# STM32F446RE_subcircuit.net
KiCad netlist of a schematic drawn in EAGLE
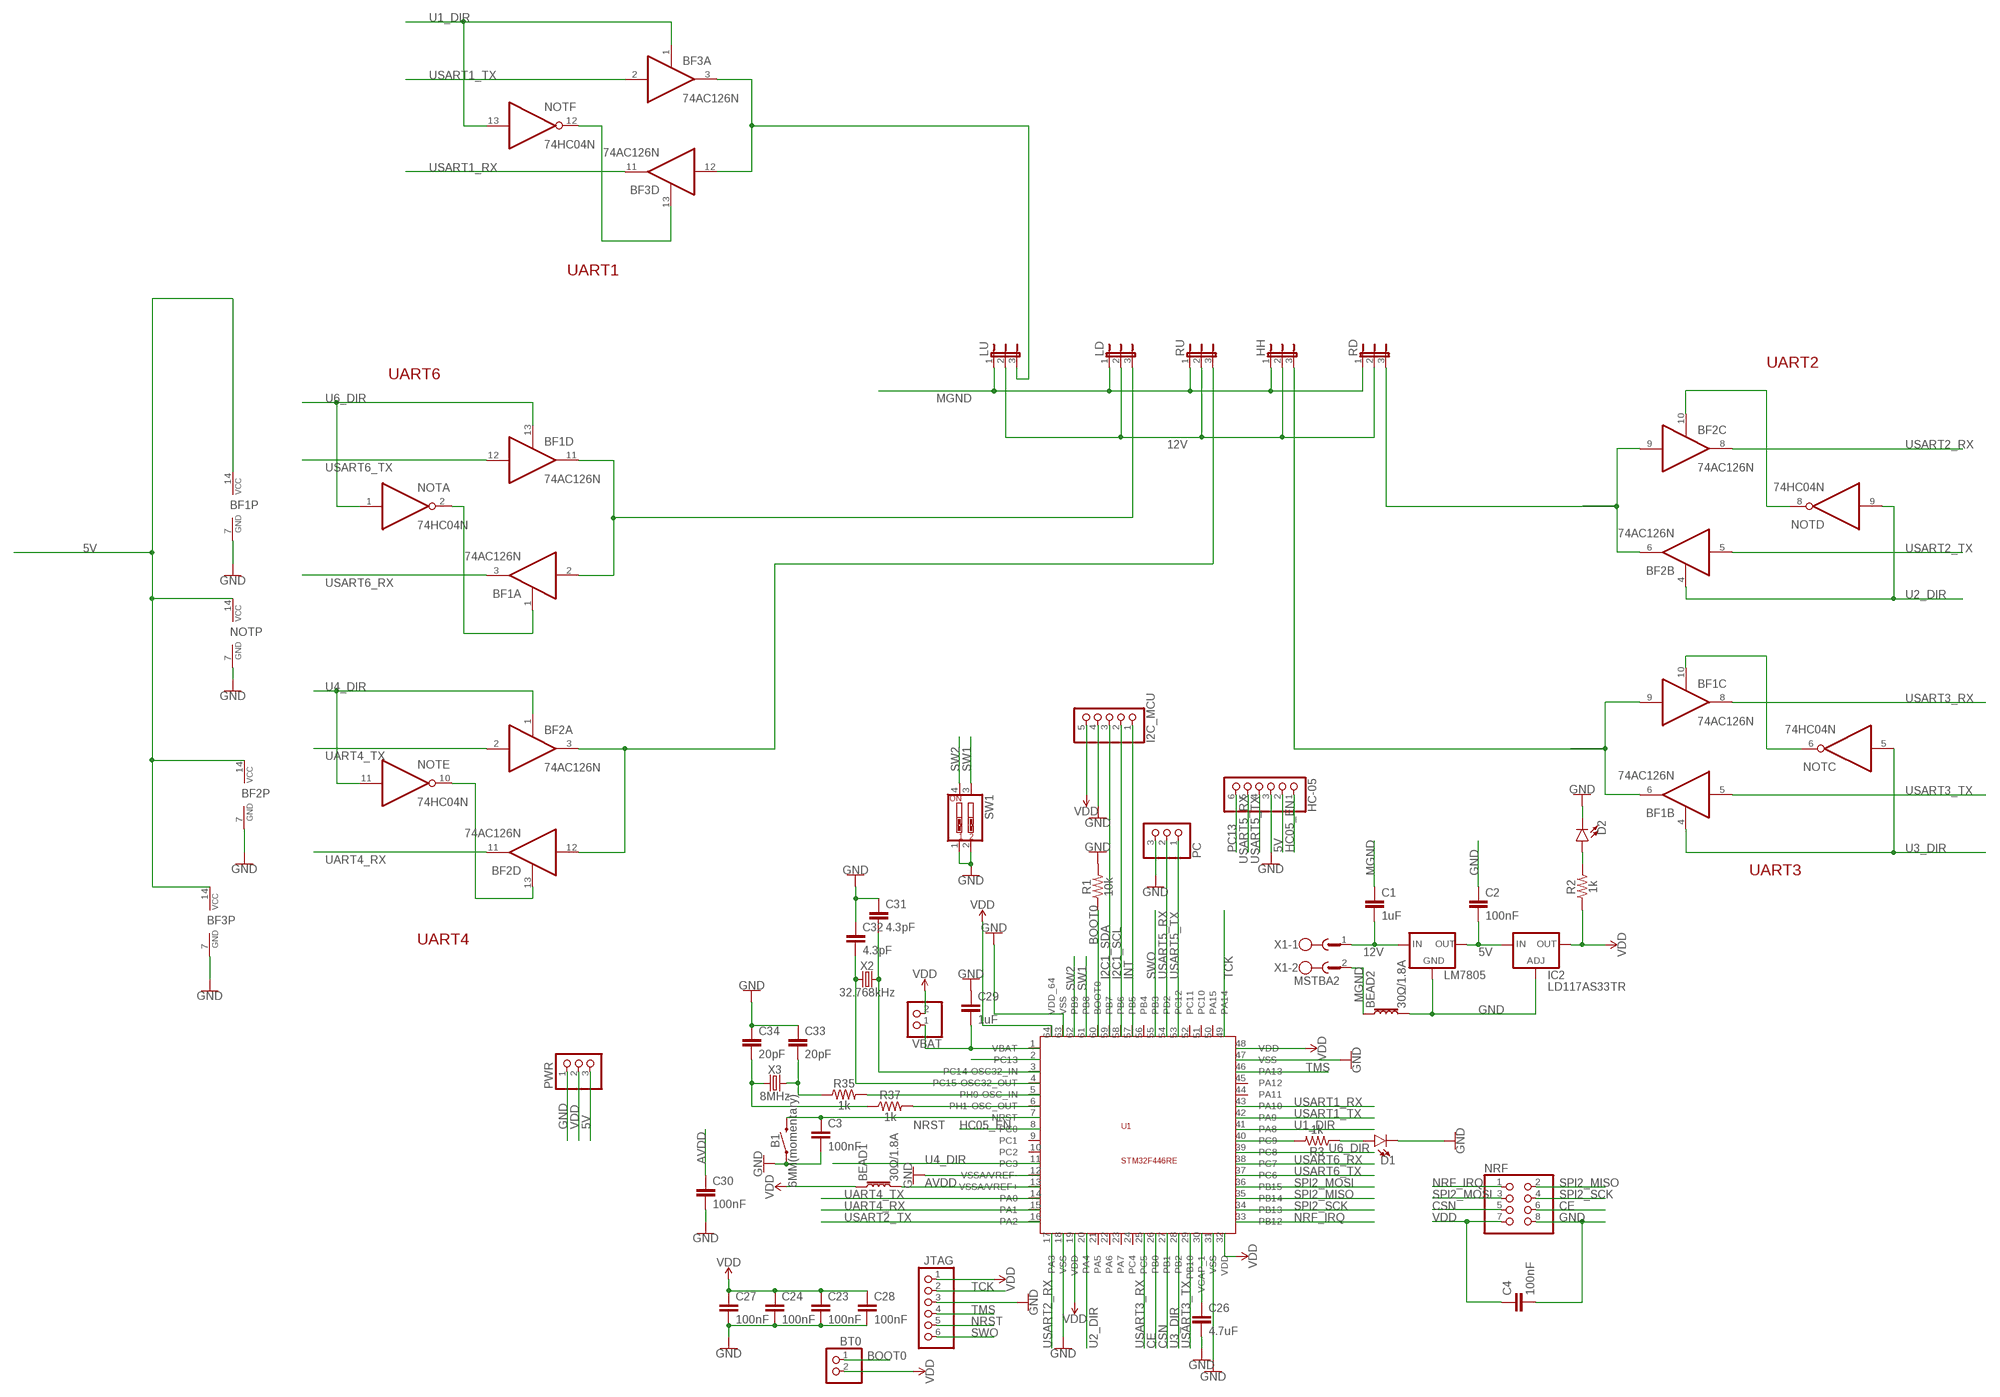
[diagram p0: schematic, sheet 1]

(export (version "E")
  (design (tool "Eeschema 10.0.6"))
  (components
    (comp (ref "B1")
      (value "6MM(momentary)")
      (footprint "eagle-import:TACTILE_SWITCH_PTH_6.0MM")
      (libsource (lib "eagle-import") (part "MOMENTARY-SWITCH-SPST-PTH-6.0MM"))
    )
    (comp (ref "BEAD1")
      (value "30Ω/1.8A")
      (footprint "eagle-import:0603")
      (libsource (lib "eagle-import") (part "FERRITE_BEAD-0603"))
    )
    (comp (ref "BEAD2")
      (value "30Ω/1.8A")
      (footprint "eagle-import:0603")
      (libsource (lib "eagle-import") (part "FERRITE_BEAD-0603"))
    )
    (comp (ref "BF1")
      (value "74AC126N")
      (footprint "eagle-import:DIL14")
      (libsource (lib "eagle-import") (part "74126NAC"))
    )
    (comp (ref "BF2")
      (value "74AC126N")
      (footprint "eagle-import:DIL14")
      (libsource (lib "eagle-import") (part "74126NAC"))
    )
    (comp (ref "BF3")
      (value "74AC126N")
      (footprint "eagle-import:DIL14")
      (libsource (lib "eagle-import") (part "74xx-eu_85_74126NAC"))
    )
    (comp (ref "BT0")
      (value "PINHD-1X2")
      (footprint "eagle-import:1X02")
      (libsource (lib "eagle-import") (part "PINHD-1X2"))
    )
    (comp (ref "C1")
      (value "1uF")
      (footprint "eagle-import:C050-030-075")
      (libsource (lib "eagle-import") (part "C5P"))
    )
    (comp (ref "C2")
      (value "100nF")
      (footprint "eagle-import:C025-030X050")
      (libsource (lib "eagle-import") (part "C2.5P"))
    )
    (comp (ref "C3")
      (value "100nF")
      (footprint "eagle-import:C025-030X050")
      (libsource (lib "eagle-import") (part "C2.5P"))
    )
    (comp (ref "C4")
      (value "100nF")
      (footprint "eagle-import:C025-030X050")
      (libsource (lib "eagle-import") (part "C2.5P"))
    )
    (comp (ref "C23")
      (value "100nF")
      (footprint "eagle-import:C025-030X050")
      (libsource (lib "eagle-import") (part "C2.5P"))
    )
    (comp (ref "C24")
      (value "100nF")
      (footprint "eagle-import:C025-030X050")
      (libsource (lib "eagle-import") (part "C2.5P"))
    )
    (comp (ref "C26")
      (value "4.7uF")
      (footprint "eagle-import:C050-030-075")
      (libsource (lib "eagle-import") (part "C5P"))
    )
    (comp (ref "C27")
      (value "100nF")
      (footprint "eagle-import:C025-030X050")
      (libsource (lib "eagle-import") (part "C2.5P"))
    )
    (comp (ref "C28")
      (value "100nF")
      (footprint "eagle-import:C025-030X050")
      (libsource (lib "eagle-import") (part "C2.5P"))
    )
    (comp (ref "C29")
      (value "1uF")
      (footprint "eagle-import:C050-030-075")
      (libsource (lib "eagle-import") (part "C5P"))
    )
    (comp (ref "C30")
      (value "100nF")
      (footprint "eagle-import:C025-030X050")
      (libsource (lib "eagle-import") (part "C2.5P"))
    )
    (comp (ref "C31")
      (value "4.3pF")
      (footprint "eagle-import:C025-030X050")
      (libsource (lib "eagle-import") (part "C2.5P"))
    )
    (comp (ref "C32")
      (value "4.3pF")
      (footprint "eagle-import:C025-030X050")
      (libsource (lib "eagle-import") (part "C2.5P"))
    )
    (comp (ref "C33")
      (value "20pF")
      (footprint "eagle-import:C025-030X050")
      (libsource (lib "eagle-import") (part "C2.5P"))
    )
    (comp (ref "C34")
      (value "20pF")
      (footprint "eagle-import:C025-030X050")
      (libsource (lib "eagle-import") (part "C2.5P"))
    )
    (comp (ref "D1")
      (value "LED5MM")
      (footprint "eagle-import:LED_5MM")
      (libsource (lib "eagle-import") (part "LED5MM"))
    )
    (comp (ref "D2")
      (value "LED5MM")
      (footprint "eagle-import:LED_5MM")
      (libsource (lib "eagle-import") (part "LED5MM"))
    )
    (comp (ref "HC-05")
      (value "PINHD-1X6")
      (footprint "eagle-import:1X06")
      (libsource (lib "eagle-import") (part "PINHD-1X6"))
    )
    (comp (ref "HH")
      (value "JP2E")
      (footprint "eagle-import:JP2")
      (libsource (lib "eagle-import") (part "JP2E"))
    )
    (comp (ref "I2C_MCU")
      (value "PINHD-1X5")
      (footprint "eagle-import:1X05")
      (libsource (lib "eagle-import") (part "PINHD-1X5"))
    )
    (comp (ref "IC2")
      (value "LD117AS33TR")
      (footprint "eagle-import:SOT223")
      (libsource (lib "eagle-import") (part "LD117A?S33TR"))
    )
    (comp (ref "JTAG")
      (value "PINHD-1X6")
      (footprint "eagle-import:1X06")
      (libsource (lib "eagle-import") (part "PINHD-1X6"))
    )
    (comp (ref "LD")
      (value "JP2E")
      (footprint "eagle-import:JP2")
      (libsource (lib "eagle-import") (part "JP2E"))
    )
    (comp (ref "LM7805")
      (value "V_REG_78XX-TO-220")
      (footprint "eagle-import:TO-220-ALT")
      (libsource (lib "eagle-import") (part "V_REG_78XX-TO-220"))
    )
    (comp (ref "LU")
      (value "JP2E")
      (footprint "eagle-import:JP2")
      (libsource (lib "eagle-import") (part "JP2E"))
    )
    (comp (ref "NOT")
      (value "74HC04N")
      (footprint "eagle-import:DIL14")
      (libsource (lib "eagle-import") (part "7404NHC"))
    )
    (comp (ref "NRF")
      (value "PINHD-2X4")
      (footprint "eagle-import:2X04")
      (libsource (lib "eagle-import") (part "PINHD-2X4"))
    )
    (comp (ref "PC")
      (value "PINHD-1X3")
      (footprint "eagle-import:1X03")
      (libsource (lib "eagle-import") (part "PINHD-1X3"))
    )
    (comp (ref "PWR")
      (value "PINHD-1X3")
      (footprint "eagle-import:1X03")
      (libsource (lib "eagle-import") (part "PINHD-1X3"))
    )
    (comp (ref "R1")
      (value "10k")
      (footprint "eagle-import:AXIAL-0.3")
      (libsource (lib "eagle-import") (part "10KOHM-HORIZ-1/4W-1%"))
    )
    (comp (ref "R2")
      (value "1k")
      (footprint "eagle-import:AXIAL-0.3")
      (libsource (lib "eagle-import") (part "1KOHM-HORIZ-1/4W-1%"))
    )
    (comp (ref "R3")
      (value "1k")
      (footprint "eagle-import:AXIAL-0.3")
      (libsource (lib "eagle-import") (part "1KOHM-HORIZ-1/4W-5%"))
    )
    (comp (ref "R35")
      (value "1k")
      (footprint "eagle-import:AXIAL-0.3")
      (libsource (lib "eagle-import") (part "10KOHM-HORIZ-1/4W-1%"))
    )
    (comp (ref "R37")
      (value "1k")
      (footprint "eagle-import:AXIAL-0.3")
      (libsource (lib "eagle-import") (part "10KOHM-HORIZ-1/4W-1%"))
    )
    (comp (ref "RD")
      (value "JP2E")
      (footprint "eagle-import:JP2")
      (libsource (lib "eagle-import") (part "JP2E"))
    )
    (comp (ref "RU")
      (value "JP2E")
      (footprint "eagle-import:JP2")
      (libsource (lib "eagle-import") (part "JP2E"))
    )
    (comp (ref "SW1")
      (value "SW_DIP-2")
      (footprint "eagle-import:EDG-02")
      (libsource (lib "eagle-import") (part "SW_DIP-2"))
    )
    (comp (ref "U1")
      (value "STM32F446RE")
      (footprint "eagle-import:QFP50P1200X1200X160-64N")
      (libsource (lib "eagle-import") (part "STM32F446RE"))
    )
    (comp (ref "VBAT")
      (value "PINHD-1X2")
      (footprint "eagle-import:1X02")
      (libsource (lib "eagle-import") (part "PINHD-1X2"))
    )
    (comp (ref "X1")
      (value "MSTBA2")
      (footprint "eagle-import:MSTBA2")
      (fields (field (name "MF") "FARNELL") (field (name "MPN") "1757242"))
      (libsource (lib "eagle-import") (part "MSTBA2"))
    )
    (comp (ref "X2")
      (value "32.768kHz")
      (footprint "eagle-import:CRYSTAL-PTH-2X6-CYL")
      (libsource (lib "eagle-import") (part "CRYSTAL-32.768KHZPTH-2X6"))
    )
    (comp (ref "X3")
      (value "8MHz")
      (footprint "eagle-import:HC49UP")
      (libsource (lib "eagle-import") (part "CRYSTAL-8MHZSMD-HC49UP"))
    )
  )
  (nets
    (net (code "1") (name "/5V") (class "Default")
      (node (ref "BF1") (pin "14") (pinfunction "VCC_14") (pintype "power_in"))
      (node (ref "BF2") (pin "14") (pinfunction "VCC_14") (pintype "power_in"))
      (node (ref "BF3") (pin "14") (pinfunction "VCC_14") (pintype "power_in"))
      (node (ref "C2") (pin "2") (pinfunction "2_2") (pintype "passive"))
      (node (ref "HC-05") (pin "2") (pinfunction "2_2") (pintype "passive"))
      (node (ref "IC2") (pin "3") (pinfunction "IN_3") (pintype "input"))
      (node (ref "LM7805") (pin "OUT") (pinfunction "OUT_OUT") (pintype "passive"))
      (node (ref "NOT") (pin "14") (pinfunction "VCC_14") (pintype "power_in"))
      (node (ref "PWR") (pin "3") (pinfunction "3_3") (pintype "passive"))
    )
    (net (code "2") (name "/12V") (class "Default")
      (node (ref "C1") (pin "2") (pinfunction "2_2") (pintype "passive"))
      (node (ref "HH") (pin "2") (pinfunction "2_2") (pintype "passive"))
      (node (ref "LD") (pin "2") (pinfunction "2_2") (pintype "passive"))
      (node (ref "LM7805") (pin "IN") (pinfunction "IN_IN") (pintype "input"))
      (node (ref "LU") (pin "2") (pinfunction "2_2") (pintype "passive"))
      (node (ref "RD") (pin "2") (pinfunction "2_2") (pintype "passive"))
      (node (ref "RU") (pin "2") (pinfunction "2_2") (pintype "passive"))
      (node (ref "X1") (pin "1") (pinfunction "1_1") (pintype "passive"))
    )
    (net (code "3") (name "/AVDD") (class "Default")
      (node (ref "BEAD1") (pin "2") (pinfunction "2_2") (pintype "passive"))
      (node (ref "C30") (pin "1") (pinfunction "1_1") (pintype "passive"))
      (node (ref "U1") (pin "13") (pinfunction "VSSA/VREF+_13") (pintype "power_in"))
    )
    (net (code "4") (name "/BOOT0") (class "Default")
      (node (ref "BT0") (pin "1") (pinfunction "1_1") (pintype "passive"))
      (node (ref "R1") (pin "P$1") (pinfunction "1_P$1") (pintype "passive"))
      (node (ref "U1") (pin "60") (pinfunction "BOOT0_60") (pintype "input"))
    )
    (net (code "5") (name "/CE") (class "Default")
      (node (ref "NRF") (pin "6") (pinfunction "6_6") (pintype "passive"))
      (node (ref "U1") (pin "26") (pinfunction "PB0_26") (pintype "bidirectional"))
    )
    (net (code "6") (name "/CSN") (class "Default")
      (node (ref "NRF") (pin "5") (pinfunction "5_5") (pintype "passive"))
      (node (ref "U1") (pin "27") (pinfunction "PB1_27") (pintype "bidirectional"))
    )
    (net (code "7") (name "/HC05_EN") (class "Default")
      (node (ref "HC-05") (pin "1") (pinfunction "1_1") (pintype "passive"))
      (node (ref "U1") (pin "8") (pinfunction "PC0_8") (pintype "bidirectional"))
    )
    (net (code "8") (name "/I2C1_SCL") (class "Default")
      (node (ref "I2C_MCU") (pin "2") (pinfunction "2_2") (pintype "passive"))
      (node (ref "U1") (pin "58") (pinfunction "PB6_58") (pintype "bidirectional"))
    )
    (net (code "9") (name "/I2C1_SDA") (class "Default")
      (node (ref "I2C_MCU") (pin "3") (pinfunction "3_3") (pintype "passive"))
      (node (ref "U1") (pin "59") (pinfunction "PB7_59") (pintype "bidirectional"))
    )
    (net (code "10") (name "/INT") (class "Default")
      (node (ref "I2C_MCU") (pin "1") (pinfunction "1_1") (pintype "passive"))
      (node (ref "U1") (pin "57") (pinfunction "PB5_57") (pintype "bidirectional"))
    )
    (net (code "11") (name "/MGND") (class "Default")
      (node (ref "BEAD2") (pin "1") (pinfunction "1_1") (pintype "passive"))
      (node (ref "C1") (pin "1") (pinfunction "1_1") (pintype "passive"))
      (node (ref "HH") (pin "1") (pinfunction "1_1") (pintype "passive"))
      (node (ref "LD") (pin "1") (pinfunction "1_1") (pintype "passive"))
      (node (ref "LU") (pin "1") (pinfunction "1_1") (pintype "passive"))
      (node (ref "RD") (pin "1") (pinfunction "1_1") (pintype "passive"))
      (node (ref "RU") (pin "1") (pinfunction "1_1") (pintype "passive"))
      (node (ref "X1") (pin "2") (pinfunction "1_2") (pintype "passive"))
    )
    (net (code "12") (name "/NRF_IRQ") (class "Default")
      (node (ref "NRF") (pin "1") (pinfunction "1_1") (pintype "passive"))
      (node (ref "U1") (pin "33") (pinfunction "PB12_33") (pintype "bidirectional"))
    )
    (net (code "13") (name "/NRST") (class "Default")
      (node (ref "B1") (pin "3") (pinfunction "2_3") (pintype "passive"))
      (node (ref "C3") (pin "1") (pinfunction "1_1") (pintype "passive"))
      (node (ref "JTAG") (pin "5") (pinfunction "5_5") (pintype "passive"))
      (node (ref "U1") (pin "7") (pinfunction "NRST_7") (pintype "bidirectional"))
    )
    (net (code "14") (name "/PC13") (class "Default")
      (node (ref "HC-05") (pin "6") (pinfunction "6_6") (pintype "passive"))
      (node (ref "U1") (pin "2") (pinfunction "PC13_2") (pintype "bidirectional"))
    )
    (net (code "15") (name "/SPI2_MISO") (class "Default")
      (node (ref "NRF") (pin "2") (pinfunction "2_2") (pintype "passive"))
      (node (ref "U1") (pin "35") (pinfunction "PB14_35") (pintype "bidirectional"))
    )
    (net (code "16") (name "/SPI2_MOSI") (class "Default")
      (node (ref "NRF") (pin "3") (pinfunction "3_3") (pintype "passive"))
      (node (ref "U1") (pin "36") (pinfunction "PB15_36") (pintype "bidirectional"))
    )
    (net (code "17") (name "/SPI2_SCK") (class "Default")
      (node (ref "NRF") (pin "4") (pinfunction "4_4") (pintype "passive"))
      (node (ref "U1") (pin "34") (pinfunction "PB13_34") (pintype "bidirectional"))
    )
    (net (code "18") (name "/SW1") (class "Default")
      (node (ref "SW1") (pin "3") (pinfunction "3_3") (pintype "passive"))
      (node (ref "U1") (pin "61") (pinfunction "PB8_61") (pintype "bidirectional"))
    )
    (net (code "19") (name "/SW2") (class "Default")
      (node (ref "SW1") (pin "4") (pinfunction "4_4") (pintype "passive"))
      (node (ref "U1") (pin "62") (pinfunction "PB9_62") (pintype "bidirectional"))
    )
    (net (code "20") (name "/SWO") (class "Default")
      (node (ref "JTAG") (pin "6") (pinfunction "6_6") (pintype "passive"))
      (node (ref "U1") (pin "55") (pinfunction "PB3_55") (pintype "bidirectional"))
    )
    (net (code "21") (name "/TCK") (class "Default")
      (node (ref "JTAG") (pin "2") (pinfunction "2_2") (pintype "passive"))
      (node (ref "U1") (pin "49") (pinfunction "PA14_49") (pintype "bidirectional"))
    )
    (net (code "22") (name "/TMS") (class "Default")
      (node (ref "JTAG") (pin "4") (pinfunction "4_4") (pintype "passive"))
      (node (ref "U1") (pin "46") (pinfunction "PA13_46") (pintype "bidirectional"))
    )
    (net (code "23") (name "/U1_DIR") (class "Default")
      (node (ref "BF3") (pin "1") (pinfunction "OE_1") (pintype "input"))
      (node (ref "NOT") (pin "13") (pinfunction "I_13") (pintype "input"))
      (node (ref "U1") (pin "41") (pinfunction "PA8_41") (pintype "bidirectional"))
    )
    (net (code "24") (name "/U2_DIR") (class "Default")
      (node (ref "BF2") (pin "4") (pinfunction "OE_4") (pintype "input"))
      (node (ref "NOT") (pin "9") (pinfunction "I_9") (pintype "input"))
      (node (ref "U1") (pin "20") (pinfunction "PA4_20") (pintype "bidirectional"))
    )
    (net (code "25") (name "/U3_DIR") (class "Default")
      (node (ref "BF1") (pin "4") (pinfunction "OE_4") (pintype "input"))
      (node (ref "NOT") (pin "5") (pinfunction "I_5") (pintype "input"))
      (node (ref "U1") (pin "28") (pinfunction "PB2_28") (pintype "bidirectional"))
    )
    (net (code "26") (name "/U4_DIR") (class "Default")
      (node (ref "BF2") (pin "1") (pinfunction "OE_1") (pintype "input"))
      (node (ref "NOT") (pin "11") (pinfunction "I_11") (pintype "input"))
      (node (ref "U1") (pin "11") (pinfunction "PC3_11") (pintype "bidirectional"))
    )
    (net (code "27") (name "/U6_DIR") (class "Default")
      (node (ref "BF1") (pin "13") (pinfunction "OE_13") (pintype "input"))
      (node (ref "NOT") (pin "1") (pinfunction "I_1") (pintype "input"))
      (node (ref "U1") (pin "39") (pinfunction "PC8_39") (pintype "bidirectional"))
    )
    (net (code "28") (name "/UART4_RX") (class "Default")
      (node (ref "BF2") (pin "11") (pinfunction "O_11") (pintype "output"))
      (node (ref "U1") (pin "15") (pinfunction "PA1_15") (pintype "bidirectional"))
    )
    (net (code "29") (name "/UART4_TX") (class "Default")
      (node (ref "BF2") (pin "2") (pinfunction "I_2") (pintype "input"))
      (node (ref "U1") (pin "14") (pinfunction "PA0_14") (pintype "bidirectional"))
    )
    (net (code "30") (name "/USART1_RX") (class "Default")
      (node (ref "BF3") (pin "11") (pinfunction "O_11") (pintype "output"))
      (node (ref "U1") (pin "43") (pinfunction "PA10_43") (pintype "bidirectional"))
    )
    (net (code "31") (name "/USART1_TX") (class "Default")
      (node (ref "BF3") (pin "2") (pinfunction "I_2") (pintype "input"))
      (node (ref "U1") (pin "42") (pinfunction "PA9_42") (pintype "bidirectional"))
    )
    (net (code "32") (name "/USART2_RX") (class "Default")
      (node (ref "BF2") (pin "8") (pinfunction "O_8") (pintype "output"))
      (node (ref "U1") (pin "17") (pinfunction "PA3_17") (pintype "bidirectional"))
    )
    (net (code "33") (name "/USART2_TX") (class "Default")
      (node (ref "BF2") (pin "5") (pinfunction "I_5") (pintype "input"))
      (node (ref "U1") (pin "16") (pinfunction "PA2_16") (pintype "bidirectional"))
    )
    (net (code "34") (name "/USART3_RX") (class "Default")
      (node (ref "BF1") (pin "8") (pinfunction "O_8") (pintype "output"))
      (node (ref "U1") (pin "25") (pinfunction "PC5_25") (pintype "bidirectional"))
    )
    (net (code "35") (name "/USART3_TX") (class "Default")
      (node (ref "BF1") (pin "5") (pinfunction "I_5") (pintype "input"))
      (node (ref "U1") (pin "29") (pinfunction "PB10_29") (pintype "bidirectional"))
    )
    (net (code "36") (name "/USART5_RX") (class "Default")
      (node (ref "HC-05") (pin "5") (pinfunction "5_5") (pintype "passive"))
      (node (ref "PC") (pin "2") (pinfunction "2_2") (pintype "passive"))
      (node (ref "U1") (pin "54") (pinfunction "PD2_54") (pintype "bidirectional"))
    )
    (net (code "37") (name "/USART5_TX") (class "Default")
      (node (ref "HC-05") (pin "4") (pinfunction "4_4") (pintype "passive"))
      (node (ref "PC") (pin "1") (pinfunction "1_1") (pintype "passive"))
      (node (ref "U1") (pin "53") (pinfunction "PC12_53") (pintype "bidirectional"))
    )
    (net (code "38") (name "/USART6_RX") (class "Default")
      (node (ref "BF1") (pin "3") (pinfunction "O_3") (pintype "output"))
      (node (ref "U1") (pin "38") (pinfunction "PC7_38") (pintype "bidirectional"))
    )
    (net (code "39") (name "/USART6_TX") (class "Default")
      (node (ref "BF1") (pin "12") (pinfunction "I_12") (pintype "input"))
      (node (ref "U1") (pin "37") (pinfunction "PC6_37") (pintype "bidirectional"))
    )
    (net (code "40") (name "GND") (class "Default")
      (node (ref "B1") (pin "1") (pinfunction "1_1") (pintype "passive"))
      (node (ref "BEAD2") (pin "2") (pinfunction "2_2") (pintype "passive"))
      (node (ref "BF1") (pin "7") (pinfunction "GND_7") (pintype "power_in"))
      (node (ref "BF2") (pin "7") (pinfunction "GND_7") (pintype "power_in"))
      (node (ref "BF3") (pin "7") (pinfunction "GND_7") (pintype "power_in"))
      (node (ref "C2") (pin "1") (pinfunction "1_1") (pintype "passive"))
      (node (ref "C23") (pin "2") (pinfunction "2_2") (pintype "passive"))
      (node (ref "C24") (pin "2") (pinfunction "2_2") (pintype "passive"))
      (node (ref "C26") (pin "2") (pinfunction "2_2") (pintype "passive"))
      (node (ref "C27") (pin "2") (pinfunction "2_2") (pintype "passive"))
      (node (ref "C28") (pin "2") (pinfunction "2_2") (pintype "passive"))
      (node (ref "C29") (pin "1") (pinfunction "1_1") (pintype "passive"))
      (node (ref "C3") (pin "2") (pinfunction "2_2") (pintype "passive"))
      (node (ref "C30") (pin "2") (pinfunction "2_2") (pintype "passive"))
      (node (ref "C31") (pin "1") (pinfunction "1_1") (pintype "passive"))
      (node (ref "C32") (pin "1") (pinfunction "1_1") (pintype "passive"))
      (node (ref "C33") (pin "1") (pinfunction "1_1") (pintype "passive"))
      (node (ref "C34") (pin "1") (pinfunction "1_1") (pintype "passive"))
      (node (ref "C4") (pin "2") (pinfunction "2_2") (pintype "passive"))
      (node (ref "D1") (pin "K") (pinfunction "C_K") (pintype "passive"))
      (node (ref "D2") (pin "K") (pinfunction "C_K") (pintype "passive"))
      (node (ref "HC-05") (pin "3") (pinfunction "3_3") (pintype "passive"))
      (node (ref "I2C_MCU") (pin "4") (pinfunction "4_4") (pintype "passive"))
      (node (ref "IC2") (pin "1") (pinfunction "ADJ_1") (pintype "input"))
      (node (ref "JTAG") (pin "3") (pinfunction "3_3") (pintype "passive"))
      (node (ref "LM7805") (pin "GND") (pinfunction "GND_GND") (pintype "input"))
      (node (ref "NOT") (pin "7") (pinfunction "GND_7") (pintype "power_in"))
      (node (ref "NRF") (pin "8") (pinfunction "8_8") (pintype "passive"))
      (node (ref "PC") (pin "3") (pinfunction "3_3") (pintype "passive"))
      (node (ref "PWR") (pin "1") (pinfunction "1_1") (pintype "passive"))
      (node (ref "R1") (pin "P$2") (pinfunction "2_P$2") (pintype "passive"))
      (node (ref "SW1") (pin "1") (pinfunction "1_1") (pintype "passive"))
      (node (ref "SW1") (pin "2") (pinfunction "2_2") (pintype "passive"))
      (node (ref "U1") (pin "12") (pinfunction "VSSA/VREF-_12") (pintype "power_in"))
      (node (ref "U1") (pin "18") (pinfunction "VSS_18") (pintype "power_in"))
      (node (ref "U1") (pin "31") (pinfunction "VSS_31") (pintype "power_in"))
      (node (ref "U1") (pin "47") (pinfunction "VSS_47") (pintype "power_in"))
      (node (ref "U1") (pin "63") (pinfunction "VSS_63") (pintype "power_in"))
    )
    (net (code "41") (name "Net-(BF1A-I)") (class "Default")
      (node (ref "BF1") (pin "11") (pinfunction "O_11") (pintype "output"))
      (node (ref "BF1") (pin "2") (pinfunction "I_2") (pintype "input"))
      (node (ref "LD") (pin "3") (pinfunction "3_3") (pintype "passive"))
    )
    (net (code "42") (name "Net-(BF1A-OE)") (class "Default")
      (node (ref "BF1") (pin "1") (pinfunction "OE_1") (pintype "input"))
      (node (ref "NOT") (pin "2") (pinfunction "O_2") (pintype "output"))
    )
    (net (code "43") (name "Net-(BF1B-O)") (class "Default")
      (node (ref "BF1") (pin "6") (pinfunction "O_6") (pintype "output"))
      (node (ref "BF1") (pin "9") (pinfunction "I_9") (pintype "input"))
      (node (ref "HH") (pin "3") (pinfunction "3_3") (pintype "passive"))
    )
    (net (code "44") (name "Net-(BF1C-OE)") (class "Default")
      (node (ref "BF1") (pin "10") (pinfunction "OE_10") (pintype "input"))
      (node (ref "NOT") (pin "6") (pinfunction "O_6") (pintype "output"))
    )
    (net (code "45") (name "Net-(BF2A-O)") (class "Default")
      (node (ref "BF2") (pin "12") (pinfunction "I_12") (pintype "input"))
      (node (ref "BF2") (pin "3") (pinfunction "O_3") (pintype "output"))
      (node (ref "RU") (pin "3") (pinfunction "3_3") (pintype "passive"))
    )
    (net (code "46") (name "Net-(BF2B-O)") (class "Default")
      (node (ref "BF2") (pin "6") (pinfunction "O_6") (pintype "output"))
      (node (ref "BF2") (pin "9") (pinfunction "I_9") (pintype "input"))
      (node (ref "RD") (pin "3") (pinfunction "3_3") (pintype "passive"))
    )
    (net (code "47") (name "Net-(BF2C-OE)") (class "Default")
      (node (ref "BF2") (pin "10") (pinfunction "OE_10") (pintype "input"))
      (node (ref "NOT") (pin "8") (pinfunction "O_8") (pintype "output"))
    )
    (net (code "48") (name "Net-(BF2D-OE)") (class "Default")
      (node (ref "BF2") (pin "13") (pinfunction "OE_13") (pintype "input"))
      (node (ref "NOT") (pin "10") (pinfunction "O_10") (pintype "output"))
    )
    (net (code "49") (name "Net-(BF3A-O)") (class "Default")
      (node (ref "BF3") (pin "12") (pinfunction "I_12") (pintype "input"))
      (node (ref "BF3") (pin "3") (pinfunction "O_3") (pintype "output"))
      (node (ref "LU") (pin "3") (pinfunction "3_3") (pintype "passive"))
    )
    (net (code "50") (name "Net-(BF3D-OE)") (class "Default")
      (node (ref "BF3") (pin "13") (pinfunction "OE_13") (pintype "input"))
      (node (ref "NOT") (pin "12") (pinfunction "O_12") (pintype "output"))
    )
    (net (code "51") (name "Net-(R2-2)") (class "Default")
      (node (ref "D2") (pin "A") (pinfunction "A_A") (pintype "passive"))
      (node (ref "R2") (pin "P$2") (pinfunction "2_P$2") (pintype "passive"))
    )
    (net (code "52") (name "Net-(R3-1)") (class "Default")
      (node (ref "D1") (pin "A") (pinfunction "A_A") (pintype "passive"))
      (node (ref "R3") (pin "P$1") (pinfunction "1_P$1") (pintype "passive"))
    )
    (net (code "53") (name "Net-(R3-2)") (class "Default")
      (node (ref "R3") (pin "P$2") (pinfunction "2_P$2") (pintype "passive"))
      (node (ref "U1") (pin "40") (pinfunction "PC9_40") (pintype "bidirectional"))
    )
    (net (code "54") (name "Net-(R35-1)") (class "Default")
      (node (ref "C33") (pin "2") (pinfunction "2_2") (pintype "passive"))
      (node (ref "R35") (pin "P$1") (pinfunction "1_P$1") (pintype "passive"))
      (node (ref "X3") (pin "2") (pinfunction "2_2") (pintype "passive"))
    )
    (net (code "55") (name "Net-(R35-2)") (class "Default")
      (node (ref "R35") (pin "P$2") (pinfunction "2_P$2") (pintype "passive"))
      (node (ref "U1") (pin "5") (pinfunction "PH0-OSC_IN_5") (pintype "input"))
    )
    (net (code "56") (name "Net-(R37-1)") (class "Default")
      (node (ref "C34") (pin "2") (pinfunction "2_2") (pintype "passive"))
      (node (ref "R37") (pin "P$1") (pinfunction "1_P$1") (pintype "passive"))
      (node (ref "X3") (pin "1") (pinfunction "1_1") (pintype "passive"))
    )
    (net (code "57") (name "Net-(R37-2)") (class "Default")
      (node (ref "R37") (pin "P$2") (pinfunction "2_P$2") (pintype "passive"))
      (node (ref "U1") (pin "6") (pinfunction "PH1-OSC_OUT_6") (pintype "output"))
    )
    (net (code "58") (name "Net-(U1-PC14-OSC32_IN)") (class "Default")
      (node (ref "C31") (pin "2") (pinfunction "2_2") (pintype "passive"))
      (node (ref "U1") (pin "3") (pinfunction "PC14-OSC32_IN_3") (pintype "input"))
      (node (ref "X2") (pin "2") (pinfunction "2_2") (pintype "passive"))
    )
    (net (code "59") (name "Net-(U1-PC15-OSC32_OUT)") (class "Default")
      (node (ref "C32") (pin "2") (pinfunction "2_2") (pintype "passive"))
      (node (ref "U1") (pin "4") (pinfunction "PC15-OSC32_OUT_4") (pintype "output"))
      (node (ref "X2") (pin "1") (pinfunction "1_1") (pintype "passive"))
    )
    (net (code "60") (name "Net-(U1-VBAT)") (class "Default")
      (node (ref "C29") (pin "2") (pinfunction "2_2") (pintype "passive"))
      (node (ref "U1") (pin "1") (pinfunction "VBAT_1") (pintype "power_in"))
      (node (ref "VBAT") (pin "1") (pinfunction "1_1") (pintype "passive"))
    )
    (net (code "61") (name "Net-(U1-VCAP_1)") (class "Default")
      (node (ref "C26") (pin "1") (pinfunction "1_1") (pintype "passive"))
      (node (ref "U1") (pin "30") (pinfunction "VCAP_1_30") (pintype "power_in"))
    )
    (net (code "62") (name "VDD") (class "Default")
      (node (ref "BEAD1") (pin "1") (pinfunction "1_1") (pintype "passive"))
      (node (ref "BT0") (pin "2") (pinfunction "2_2") (pintype "passive"))
      (node (ref "C23") (pin "1") (pinfunction "1_1") (pintype "passive"))
      (node (ref "C24") (pin "1") (pinfunction "1_1") (pintype "passive"))
      (node (ref "C27") (pin "1") (pinfunction "1_1") (pintype "passive"))
      (node (ref "C28") (pin "1") (pinfunction "1_1") (pintype "passive"))
      (node (ref "C4") (pin "1") (pinfunction "1_1") (pintype "passive"))
      (node (ref "I2C_MCU") (pin "5") (pinfunction "5_5") (pintype "passive"))
      (node (ref "IC2") (pin "4") (pinfunction "OUT_4") (pintype "passive"))
      (node (ref "JTAG") (pin "1") (pinfunction "1_1") (pintype "passive"))
      (node (ref "NRF") (pin "7") (pinfunction "7_7") (pintype "passive"))
      (node (ref "PWR") (pin "2") (pinfunction "2_2") (pintype "passive"))
      (node (ref "R2") (pin "P$1") (pinfunction "1_P$1") (pintype "passive"))
      (node (ref "U1") (pin "19") (pinfunction "VDD_19") (pintype "power_in"))
      (node (ref "U1") (pin "32") (pinfunction "VDD_32") (pintype "power_in"))
      (node (ref "U1") (pin "48") (pinfunction "VDD_48") (pintype "power_in"))
      (node (ref "U1") (pin "64") (pinfunction "VDD_64_64") (pintype "power_in"))
      (node (ref "VBAT") (pin "2") (pinfunction "2_2") (pintype "passive"))
    )
    (net (code "63") (name "unconnected-(U1-PA5-Pad21)") (class "Default")
      (node (ref "U1") (pin "21") (pinfunction "PA5_21") (pintype "bidirectional"))
    )
    (net (code "64") (name "unconnected-(U1-PA6-Pad22)") (class "Default")
      (node (ref "U1") (pin "22") (pinfunction "PA6_22") (pintype "bidirectional"))
    )
    (net (code "65") (name "unconnected-(U1-PA7-Pad23)") (class "Default")
      (node (ref "U1") (pin "23") (pinfunction "PA7_23") (pintype "bidirectional"))
    )
    (net (code "66") (name "unconnected-(U1-PA11-Pad44)") (class "Default")
      (node (ref "U1") (pin "44") (pinfunction "PA11_44") (pintype "bidirectional"))
    )
    (net (code "67") (name "unconnected-(U1-PA12-Pad45)") (class "Default")
      (node (ref "U1") (pin "45") (pinfunction "PA12_45") (pintype "bidirectional"))
    )
    (net (code "68") (name "unconnected-(U1-PA15-Pad50)") (class "Default")
      (node (ref "U1") (pin "50") (pinfunction "PA15_50") (pintype "bidirectional"))
    )
    (net (code "69") (name "unconnected-(U1-PB4-Pad56)") (class "Default")
      (node (ref "U1") (pin "56") (pinfunction "PB4_56") (pintype "bidirectional"))
    )
    (net (code "70") (name "unconnected-(U1-PC1-Pad9)") (class "Default")
      (node (ref "U1") (pin "9") (pinfunction "PC1_9") (pintype "bidirectional"))
    )
    (net (code "71") (name "unconnected-(U1-PC2-Pad10)") (class "Default")
      (node (ref "U1") (pin "10") (pinfunction "PC2_10") (pintype "bidirectional"))
    )
    (net (code "72") (name "unconnected-(U1-PC4-Pad24)") (class "Default")
      (node (ref "U1") (pin "24") (pinfunction "PC4_24") (pintype "bidirectional"))
    )
    (net (code "73") (name "unconnected-(U1-PC10-Pad51)") (class "Default")
      (node (ref "U1") (pin "51") (pinfunction "PC10_51") (pintype "bidirectional"))
    )
    (net (code "74") (name "unconnected-(U1-PC11-Pad52)") (class "Default")
      (node (ref "U1") (pin "52") (pinfunction "PC11_52") (pintype "bidirectional"))
    )
  )
)
